# MCU.net
KiCad netlist of a schematic drawn in Altium Designer
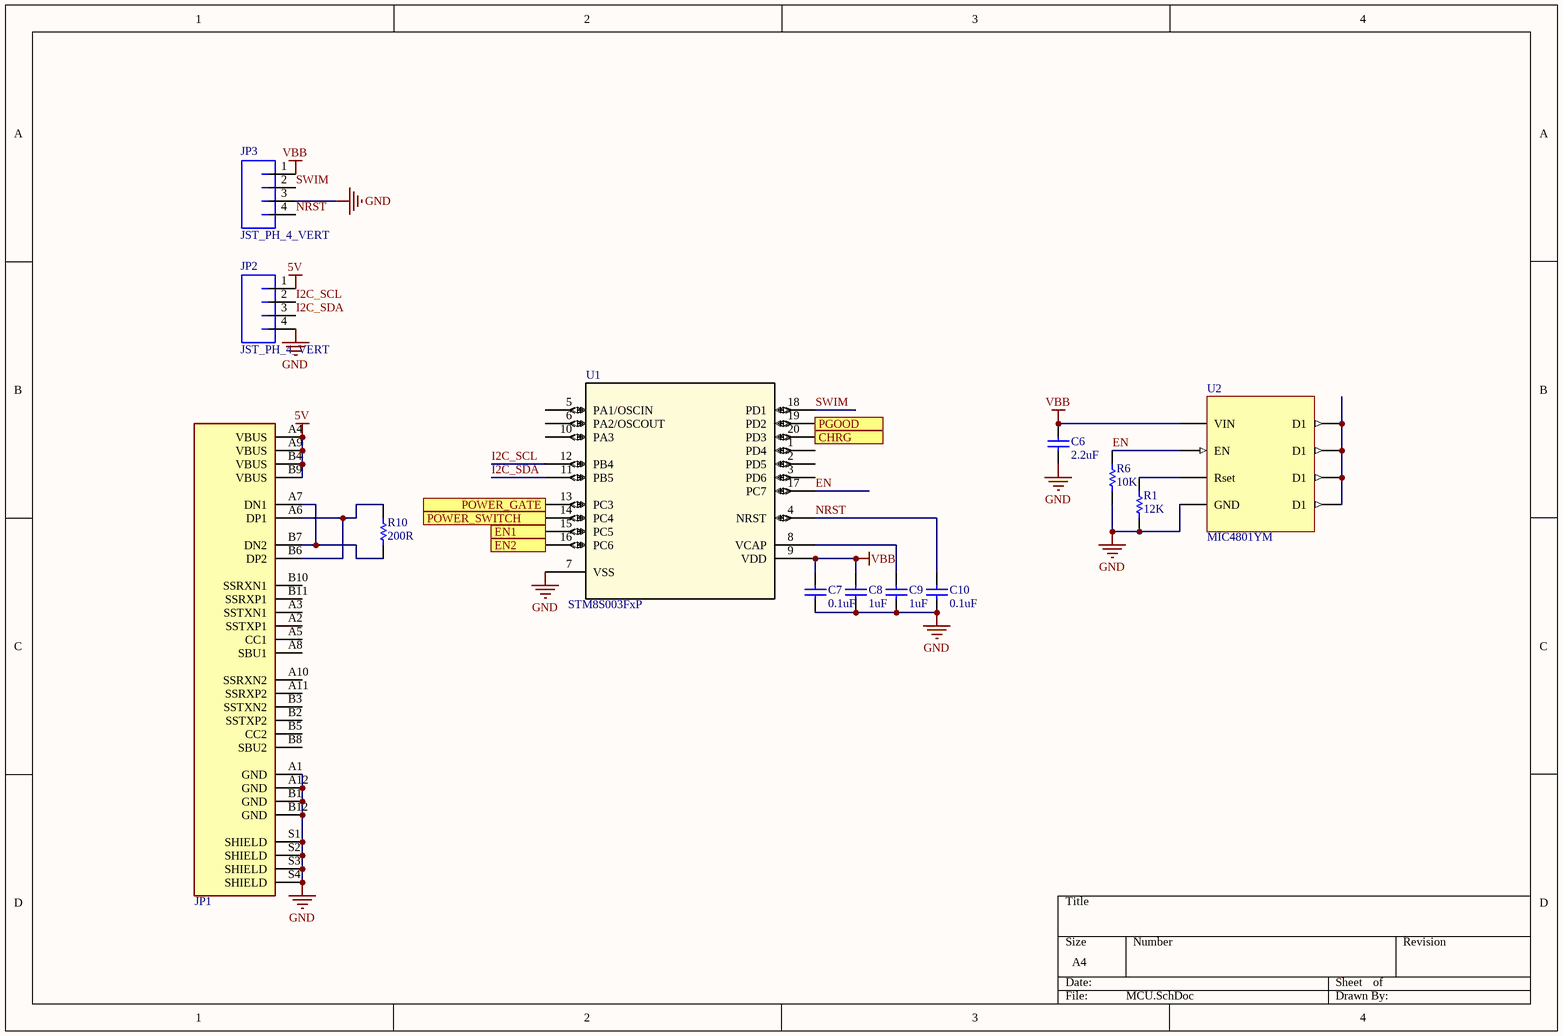
[diagram p0: MCU.SchDoc]

(export (version "E")
  (design (tool "Eeschema 10.0.6"))
  (components
    (comp (ref "C6")
      (value "2.2uF")
      (footprint "C0603[1608X92]")
      (description "2.2uF 6.3V 10% 0603 (1608 Metric)")
      (fields (field (name "PARTNUMBER") "GRM185R60J225KE26D") (field (name "MANUFACTURER") "Murata"))
      (libsource (lib "Capacitors") (part "CAP_2.2uF_6.3V_0603_10%"))
    )
    (comp (ref "C7")
      (value "0.1uF")
      (footprint "C0603[1608X92]")
      (description "0.1uF 6.3V 10% 0603 (1608 Metric)")
      (fields (field (name "PARTNUMBER") "GRM188R70J104KA01D") (field (name "MANUFACTURER") "Murata"))
      (libsource (lib "Capacitors") (part "CAP_0.1uF_6.3V_0603_10%"))
    )
    (comp (ref "C8")
      (value "1uF")
      (footprint "C0603[1608X92]")
      (description "1uF 6.3V 10% 0603 (1608 Metric)")
      (fields (field (name "PARTNUMBER") "GRM188R60J105KA01D") (field (name "MANUFACTURER") "Murata"))
      (libsource (lib "Capacitors") (part "CAP_1uF_6.3V_0603_10%"))
    )
    (comp (ref "C9")
      (value "1uF")
      (footprint "C0603[1608X92]")
      (description "1uF 6.3V 10% 0603 (1608 Metric)")
      (fields (field (name "PARTNUMBER") "GRM188R60J105KA01D") (field (name "MANUFACTURER") "Murata"))
      (libsource (lib "Capacitors") (part "CAP_1uF_6.3V_0603_10%"))
    )
    (comp (ref "C10")
      (value "0.1uF")
      (footprint "C0603[1608X92]")
      (description "0.1uF 6.3V 10% 0603 (1608 Metric)")
      (fields (field (name "PARTNUMBER") "GRM188R70J104KA01D") (field (name "MANUFACTURER") "Murata"))
      (libsource (lib "Capacitors") (part "CAP_0.1uF_6.3V_0603_10%"))
    )
    (comp (ref "JP1")
      (value "UJ31-CH-3-MSMT-TR-67")
      (footprint "CUI_UJ31-CH-3-MSMT-TR-67")
      (description "Type C, USB 3.1 Gen 2, 5 A, Right Angle, Mid Mount _SMT_,  Waterproof, USB Receptacle")
      (fields (field (name "MANUFACTURER") "CUI Devices") (field (name "PARTNUMBER") "UJ31-CH-3-MSMT-TR"))
      (libsource (lib "Connectors") (part "UJ31-CH-3-MSMT-TR-67"))
    )
    (comp (ref "JP2")
      (value "JST_PH_4_VERT")
      (footprint "JST-PH-4-PTH-VERT")
      (fields
        (field (name "PARTNUMBER") "B4B-PH-K-S(LF)(SN)")
        (field (name "MANUFACTURER") "JST Sales America Inc.")
      )
      (libsource (lib "Connectors") (part "JST_PH_4_VERT"))
    )
    (comp (ref "JP3")
      (value "JST_PH_4_VERT")
      (footprint "JST-PH-4-PTH-VERT")
      (fields
        (field (name "PARTNUMBER") "B4B-PH-K-S(LF)(SN)")
        (field (name "MANUFACTURER") "JST Sales America Inc.")
      )
      (libsource (lib "Connectors") (part "JST_PH_4_VERT"))
    )
    (comp (ref "R1")
      (value "12K")
      (footprint "R0603[1608]")
      (description "12K 0.25W 1% 0603 (1005 Metric)")
      (fields (field (name "MANUFACTURER") "Vishay") (field (name "PARTNUMBER") "RCS060312K0FKEA"))
      (libsource (lib "Resistors") (part "RES_12K_0603_1%"))
    )
    (comp (ref "R6")
      (value "10K")
      (footprint "R0603[1608]")
      (description "10K 0.25W 1% 0603 (1005 Metric)")
      (fields (field (name "MANUFACTURER") "Vishay / Dale") (field (name "PARTNUMBER") "CRCW060310K0FKEAHP"))
      (libsource (lib "Resistors") (part "RES_10K_0603_1%"))
    )
    (comp (ref "R10")
      (value "200R")
      (footprint "R0603[1608]")
      (description "200R 0.25W 1% 0603 (1005 Metric)")
      (fields (field (name "MANUFACTURER") "Vishay / Dale") (field (name "PARTNUMBER") "CRCW0603200RFKEAHP"))
      (libsource (lib "Resistors") (part "RES_200R_0603_1%"))
    )
    (comp (ref "U1")
      (value "STM8S003FxP")
      (footprint "TSSOP-20")
      (description "8-bit MCU with 8 Kbytes Flash, 16 MHz CPU, integrated EEPROM")
      (fields (field (name "MANUFACTURER") "STMicroelectronics"))
      (libsource (lib "ICs") (part "STM8S003FxP"))
    )
    (comp (ref "U2")
      (value "MIC4801YM")
      (footprint "SOIC-8")
      (description "600mA Single Channel WLED Driver w/ Ultrafast PWM Control")
      (fields (field (name "MANUFACTURER") "Microchips"))
      (libsource (lib "ICs") (part "MIC4801"))
    )
  )
  (nets
    (net (code "1") (name "/CHRG") (class "Default")
      (node (ref "U1") (pin "20") (pinfunction "PD3_20") (pintype "bidirectional"))
    )
    (net (code "2") (name "/EN") (class "Default")
      (node (ref "R6") (pin "2") (pinfunction "2_2") (pintype "passive"))
      (node (ref "U1") (pin "17") (pinfunction "PC7_17") (pintype "bidirectional"))
      (node (ref "U2") (pin "2") (pinfunction "EN_2") (pintype "input"))
    )
    (net (code "3") (name "/EN1") (class "Default")
      (node (ref "U1") (pin "15") (pinfunction "PC5_15") (pintype "bidirectional"))
    )
    (net (code "4") (name "/EN2") (class "Default")
      (node (ref "U1") (pin "16") (pinfunction "PC6_16") (pintype "bidirectional"))
    )
    (net (code "5") (name "/I2C_SCL") (class "Default")
      (node (ref "JP2") (pin "2") (pinfunction "2_2") (pintype "passive"))
      (node (ref "U1") (pin "12") (pinfunction "PB4_12") (pintype "bidirectional"))
    )
    (net (code "6") (name "/I2C_SDA") (class "Default")
      (node (ref "JP2") (pin "3") (pinfunction "3_3") (pintype "passive"))
      (node (ref "U1") (pin "11") (pinfunction "PB5_11") (pintype "bidirectional"))
    )
    (net (code "7") (name "/NRST") (class "Default")
      (node (ref "C10") (pin "2") (pinfunction "2_2") (pintype "passive"))
      (node (ref "JP3") (pin "4") (pinfunction "4_4") (pintype "passive"))
      (node (ref "U1") (pin "4") (pinfunction "NRST_4") (pintype "bidirectional"))
    )
    (net (code "8") (name "/PGOOD") (class "Default")
      (node (ref "U1") (pin "19") (pinfunction "PD2_19") (pintype "bidirectional"))
    )
    (net (code "9") (name "/POWER_GATE") (class "Default")
      (node (ref "U1") (pin "13") (pinfunction "PC3_13") (pintype "bidirectional"))
    )
    (net (code "10") (name "/POWER_SWITCH") (class "Default")
      (node (ref "U1") (pin "14") (pinfunction "PC4_14") (pintype "bidirectional"))
    )
    (net (code "11") (name "/SWIM") (class "Default")
      (node (ref "JP3") (pin "2") (pinfunction "2_2") (pintype "passive"))
      (node (ref "U1") (pin "18") (pinfunction "PD1_18") (pintype "bidirectional"))
    )
    (net (code "12") (name "5V") (class "Default")
      (node (ref "JP1") (pin "A4") (pinfunction "VBUS_A4") (pintype "passive"))
      (node (ref "JP1") (pin "A9") (pinfunction "VBUS_A9") (pintype "passive"))
      (node (ref "JP1") (pin "B4") (pinfunction "VBUS_B4") (pintype "passive"))
      (node (ref "JP1") (pin "B9") (pinfunction "VBUS_B9") (pintype "passive"))
      (node (ref "JP2") (pin "1") (pinfunction "1_1") (pintype "passive"))
    )
    (net (code "13") (name "GND") (class "Default")
      (node (ref "C10") (pin "1") (pinfunction "1_1") (pintype "passive"))
      (node (ref "C6") (pin "1") (pinfunction "1_1") (pintype "passive"))
      (node (ref "C7") (pin "1") (pinfunction "1_1") (pintype "passive"))
      (node (ref "C8") (pin "2") (pinfunction "2_2") (pintype "passive"))
      (node (ref "C9") (pin "2") (pinfunction "2_2") (pintype "passive"))
      (node (ref "JP1") (pin "A1") (pinfunction "GND_A1") (pintype "passive"))
      (node (ref "JP1") (pin "A12") (pinfunction "GND_A12") (pintype "passive"))
      (node (ref "JP1") (pin "B1") (pinfunction "GND_B1") (pintype "passive"))
      (node (ref "JP1") (pin "B12") (pinfunction "GND_B12") (pintype "passive"))
      (node (ref "JP1") (pin "S1") (pinfunction "SHIELD_S1") (pintype "passive"))
      (node (ref "JP1") (pin "S2") (pinfunction "SHIELD_S2") (pintype "passive"))
      (node (ref "JP1") (pin "S3") (pinfunction "SHIELD_S3") (pintype "passive"))
      (node (ref "JP1") (pin "S4") (pinfunction "SHIELD_S4") (pintype "passive"))
      (node (ref "JP2") (pin "4") (pinfunction "4_4") (pintype "passive"))
      (node (ref "JP3") (pin "3") (pinfunction "3_3") (pintype "passive"))
      (node (ref "R1") (pin "1") (pinfunction "1_1") (pintype "passive"))
      (node (ref "R6") (pin "1") (pinfunction "1_1") (pintype "passive"))
      (node (ref "U1") (pin "7") (pinfunction "VSS_7") (pintype "power_in"))
      (node (ref "U2") (pin "4") (pinfunction "GND_4") (pintype "power_in"))
    )
    (net (code "14") (name "Net-(JP1-DN1)") (class "Default")
      (node (ref "JP1") (pin "A7") (pinfunction "DN1_A7") (pintype "passive"))
      (node (ref "JP1") (pin "B7") (pinfunction "DN2_B7") (pintype "passive"))
      (node (ref "R10") (pin "1") (pinfunction "1_1") (pintype "passive"))
    )
    (net (code "15") (name "Net-(JP1-DP1)") (class "Default")
      (node (ref "JP1") (pin "A6") (pinfunction "DP1_A6") (pintype "passive"))
      (node (ref "JP1") (pin "B6") (pinfunction "DP2_B6") (pintype "passive"))
      (node (ref "R10") (pin "2") (pinfunction "2_2") (pintype "passive"))
    )
    (net (code "16") (name "Net-(U1-VCAP)") (class "Default")
      (node (ref "C9") (pin "1") (pinfunction "1_1") (pintype "passive"))
      (node (ref "U1") (pin "8") (pinfunction "VCAP_8") (pintype "power_in"))
    )
    (net (code "17") (name "Net-(U2-D1-Pad5)") (class "Default")
      (node (ref "U2") (pin "5") (pinfunction "D1_5") (pintype "output"))
      (node (ref "U2") (pin "6") (pinfunction "D1_6") (pintype "output"))
      (node (ref "U2") (pin "7") (pinfunction "D1_7") (pintype "output"))
      (node (ref "U2") (pin "8") (pinfunction "D1_8") (pintype "output"))
    )
    (net (code "18") (name "Net-(U2-Rset)") (class "Default")
      (node (ref "R1") (pin "2") (pinfunction "2_2") (pintype "passive"))
      (node (ref "U2") (pin "3") (pinfunction "Rset_3") (pintype "passive"))
    )
    (net (code "19") (name "VBB") (class "Default")
      (node (ref "C6") (pin "2") (pinfunction "2_2") (pintype "passive"))
      (node (ref "C7") (pin "2") (pinfunction "2_2") (pintype "passive"))
      (node (ref "C8") (pin "1") (pinfunction "1_1") (pintype "passive"))
      (node (ref "JP3") (pin "1") (pinfunction "1_1") (pintype "passive"))
      (node (ref "U1") (pin "9") (pinfunction "VDD_9") (pintype "power_in"))
      (node (ref "U2") (pin "1") (pinfunction "VIN_1") (pintype "power_in"))
    )
    (net (code "20") (name "unconnected-(JP1-CC1-PadA5)") (class "Default")
      (node (ref "JP1") (pin "A5") (pinfunction "CC1_A5") (pintype "passive"))
    )
    (net (code "21") (name "unconnected-(JP1-CC2-PadB5)") (class "Default")
      (node (ref "JP1") (pin "B5") (pinfunction "CC2_B5") (pintype "passive"))
    )
    (net (code "22") (name "unconnected-(JP1-SBU1-PadA8)") (class "Default")
      (node (ref "JP1") (pin "A8") (pinfunction "SBU1_A8") (pintype "passive"))
    )
    (net (code "23") (name "unconnected-(JP1-SBU2-PadB8)") (class "Default")
      (node (ref "JP1") (pin "B8") (pinfunction "SBU2_B8") (pintype "passive"))
    )
    (net (code "24") (name "unconnected-(JP1-SSRXN1-PadB10)") (class "Default")
      (node (ref "JP1") (pin "B10") (pinfunction "SSRXN1_B10") (pintype "passive"))
    )
    (net (code "25") (name "unconnected-(JP1-SSRXN2-PadA10)") (class "Default")
      (node (ref "JP1") (pin "A10") (pinfunction "SSRXN2_A10") (pintype "passive"))
    )
    (net (code "26") (name "unconnected-(JP1-SSRXP1-PadB11)") (class "Default")
      (node (ref "JP1") (pin "B11") (pinfunction "SSRXP1_B11") (pintype "passive"))
    )
    (net (code "27") (name "unconnected-(JP1-SSRXP2-PadA11)") (class "Default")
      (node (ref "JP1") (pin "A11") (pinfunction "SSRXP2_A11") (pintype "passive"))
    )
    (net (code "28") (name "unconnected-(JP1-SSTXN1-PadA3)") (class "Default")
      (node (ref "JP1") (pin "A3") (pinfunction "SSTXN1_A3") (pintype "passive"))
    )
    (net (code "29") (name "unconnected-(JP1-SSTXN2-PadB3)") (class "Default")
      (node (ref "JP1") (pin "B3") (pinfunction "SSTXN2_B3") (pintype "passive"))
    )
    (net (code "30") (name "unconnected-(JP1-SSTXP1-PadA2)") (class "Default")
      (node (ref "JP1") (pin "A2") (pinfunction "SSTXP1_A2") (pintype "passive"))
    )
    (net (code "31") (name "unconnected-(JP1-SSTXP2-PadB2)") (class "Default")
      (node (ref "JP1") (pin "B2") (pinfunction "SSTXP2_B2") (pintype "passive"))
    )
    (net (code "32") (name "unconnected-(U1-PA1{slash}OSCIN-Pad5)") (class "Default")
      (node (ref "U1") (pin "5") (pinfunction "PA1/OSCIN_5") (pintype "bidirectional"))
    )
    (net (code "33") (name "unconnected-(U1-PA2{slash}OSCOUT-Pad6)") (class "Default")
      (node (ref "U1") (pin "6") (pinfunction "PA2/OSCOUT_6") (pintype "bidirectional"))
    )
    (net (code "34") (name "unconnected-(U1-PA3-Pad10)") (class "Default")
      (node (ref "U1") (pin "10") (pinfunction "PA3_10") (pintype "bidirectional"))
    )
    (net (code "35") (name "unconnected-(U1-PD4-Pad1)") (class "Default")
      (node (ref "U1") (pin "1") (pinfunction "PD4_1") (pintype "bidirectional"))
    )
    (net (code "36") (name "unconnected-(U1-PD5-Pad2)") (class "Default")
      (node (ref "U1") (pin "2") (pinfunction "PD5_2") (pintype "bidirectional"))
    )
    (net (code "37") (name "unconnected-(U1-PD6-Pad3)") (class "Default")
      (node (ref "U1") (pin "3") (pinfunction "PD6_3") (pintype "bidirectional"))
    )
  )
)
